# XL_N76E003K3__POWER_V17.net
KiCad netlist of a schematic drawn in Altium Designer
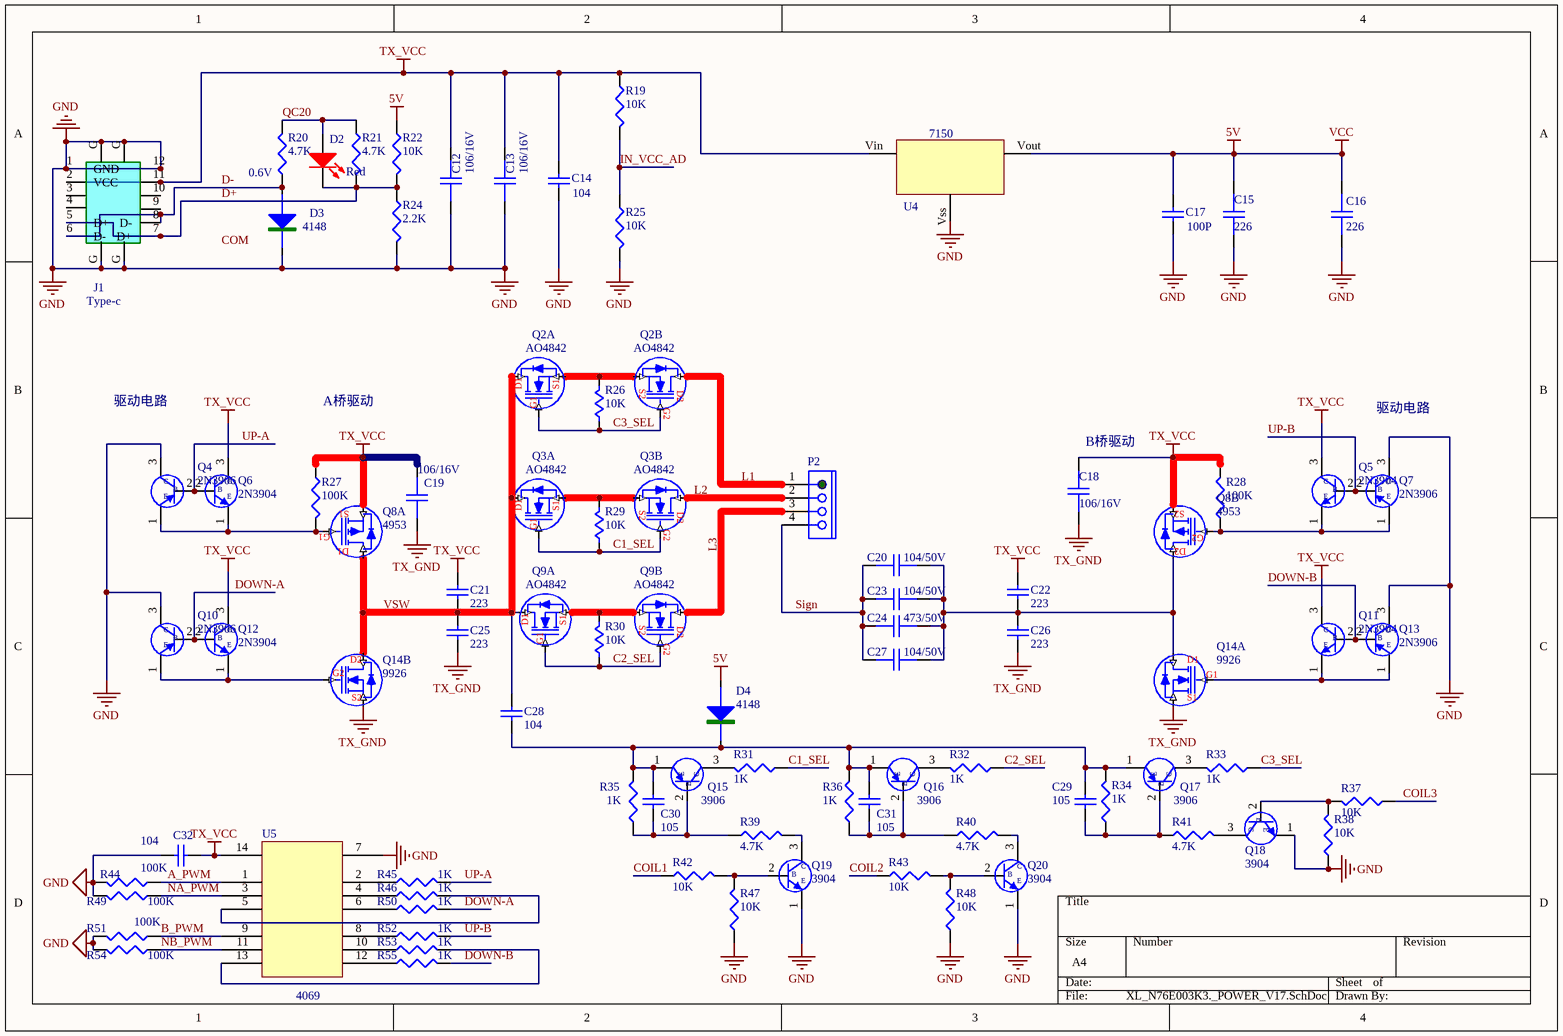
[diagram p0: XL_N76E003K3._POWER_V17.SchDoc]

(export (version "E")
  (design (tool "Eeschema 10.0.6"))
  (components
    (comp (ref "C12") (value "106/16V") (footprint "C0805") (libsource (lib "*") (part "CH")))
    (comp (ref "C13") (value "106/16V") (footprint "C0805") (libsource (lib "*") (part "CH")))
    (comp (ref "C14")
      (value "104")
      (footprint "C0402")
      (description "Capacitor")
      (fields (field (name "PUBLISHER") "Altium Limited"))
      (libsource (lib "*") (part "Cap"))
    )
    (comp (ref "C15") (value "226") (footprint "C0805") (libsource (lib "*") (part "CH")))
    (comp (ref "C16") (value "226") (footprint "C0805") (libsource (lib "*") (part "CH")))
    (comp (ref "C17")
      (value "100P")
      (footprint "C0402")
      (description "Capacitor")
      (fields (field (name "PUBLISHER") "Altium Limited"))
      (libsource (lib "*") (part "Cap"))
    )
    (comp (ref "C18") (value "106/16V") (footprint "C0805") (libsource (lib "*") (part "CH")))
    (comp (ref "C19") (value "106/16V") (footprint "C0805") (libsource (lib "*") (part "CH")))
    (comp (ref "C20") (value "104/50V") (footprint "C1206") (libsource (lib "*") (part "CH")))
    (comp (ref "C21")
      (value "223")
      (footprint "C1206")
      (description "Capacitor")
      (fields (field (name "PUBLISHER") "Altium Limited"))
      (libsource (lib "*") (part "Cap"))
    )
    (comp (ref "C22")
      (value "223")
      (footprint "C1206")
      (description "Capacitor")
      (fields (field (name "PUBLISHER") "Altium Limited"))
      (libsource (lib "*") (part "Cap"))
    )
    (comp (ref "C23") (value "104/50V") (footprint "C1206") (libsource (lib "*") (part "CH")))
    (comp (ref "C24") (value "473/50V") (footprint "C1206") (libsource (lib "*") (part "CH")))
    (comp (ref "C25")
      (value "223")
      (footprint "C0402")
      (description "Capacitor")
      (fields (field (name "PUBLISHER") "Altium Limited"))
      (libsource (lib "*") (part "Cap"))
    )
    (comp (ref "C26")
      (value "223")
      (footprint "C1206")
      (description "Capacitor")
      (fields (field (name "PUBLISHER") "Altium Limited"))
      (libsource (lib "*") (part "Cap"))
    )
    (comp (ref "C27") (value "104/50V") (footprint "C1206") (libsource (lib "*") (part "CH")))
    (comp (ref "C28")
      (value "104")
      (footprint "C0402")
      (description "Capacitor")
      (fields (field (name "PUBLISHER") "Altium Limited"))
      (libsource (lib "*") (part "Cap"))
    )
    (comp (ref "C29")
      (value "105")
      (footprint "C0402")
      (description "Capacitor")
      (fields (field (name "PUBLISHER") "Altium Limited"))
      (libsource (lib "*") (part "Cap"))
    )
    (comp (ref "C30")
      (value "105")
      (footprint "C0402")
      (description "Capacitor")
      (fields (field (name "PUBLISHER") "Altium Limited"))
      (libsource (lib "*") (part "Cap"))
    )
    (comp (ref "C31")
      (value "105")
      (footprint "C0402")
      (description "Capacitor")
      (fields (field (name "PUBLISHER") "Altium Limited"))
      (libsource (lib "*") (part "Cap"))
    )
    (comp (ref "C32")
      (value "104")
      (footprint "C0402")
      (description "Capacitor")
      (fields (field (name "PUBLISHER") "Altium Limited"))
      (libsource (lib "*") (part "Cap"))
    )
    (comp (ref "D2") (value "Red") (footprint "LED0603") (libsource (lib "XiaoQiang") (part "LED02")))
    (comp (ref "D3")
      (value "4148")
      (footprint "SOD323")
      (description "1N4001")
      (libsource (lib "*") (part "D0"))
    )
    (comp (ref "D4")
      (value "4148")
      (footprint "SOD323")
      (description "1N4001")
      (libsource (lib "*") (part "D0"))
    )
    (comp (ref "J1") (value "Type-c") (footprint "USB -MRO17") (libsource (lib "Xin Lang") (part "USP12P")))
    (comp (ref "P2") (value "~") (footprint "USB -MRO18-2") (libsource (lib "Xin Lang") (part "CON4")))
    (comp (ref "Q2") (value "AO4842") (footprint "SOP8D") (libsource (lib "lxzschlib") (part "MOSFETN2")))
    (comp (ref "Q3") (value "AO4842") (footprint "SOP8D") (libsource (lib "lxzschlib") (part "MOSFETN2")))
    (comp (ref "Q4") (value "2N3906") (footprint "SOT-23") (libsource (lib "Xin Lang") (part "PNP01")))
    (comp (ref "Q5") (value "2N3904") (footprint "SOT-23") (libsource (lib "Xin Lang") (part "NPN01")))
    (comp (ref "Q6") (value "2N3904") (footprint "SOT-23") (libsource (lib "") (part "NPN01_1")))
    (comp (ref "Q7") (value "2N3906") (footprint "SOT-23") (libsource (lib "") (part "PNP01_1")))
    (comp (ref "Q8") (value "4953") (footprint "SOP8D") (libsource (lib "lxzschlib") (part "MOSFETP2")))
    (comp (ref "Q9") (value "AO4842") (footprint "SOP8D") (libsource (lib "") (part "MOSFETN2_1")))
    (comp (ref "Q10") (value "2N3906") (footprint "SOT-23") (libsource (lib "Xin Lang") (part "PNP01")))
    (comp (ref "Q11") (value "2N3904") (footprint "SOT-23") (libsource (lib "Xin Lang") (part "NPN01")))
    (comp (ref "Q12") (value "2N3904") (footprint "SOT-23") (libsource (lib "") (part "NPN01_1")))
    (comp (ref "Q13") (value "2N3906") (footprint "SOT-23") (libsource (lib "") (part "PNP01_1")))
    (comp (ref "Q14") (value "9926") (footprint "SOP8D") (libsource (lib "") (part "MOSFETN2_1")))
    (comp (ref "Q15") (value "3906") (footprint "SOT-23") (libsource (lib "XiaoQiang") (part "PNP01")))
    (comp (ref "Q16") (value "3906") (footprint "SOT-23") (libsource (lib "XiaoQiang") (part "PNP01")))
    (comp (ref "Q17") (value "3906") (footprint "SOT-23") (libsource (lib "XiaoQiang") (part "PNP01")))
    (comp (ref "Q18") (value "3904") (footprint "SOT-23") (libsource (lib "") (part "NPN01_1")))
    (comp (ref "Q19") (value "3904") (footprint "SOT-23") (libsource (lib "XiaoQiang") (part "NPN01")))
    (comp (ref "Q20") (value "3904") (footprint "SOT-23") (libsource (lib "XiaoQiang") (part "NPN01")))
    (comp (ref "R19") (value "10K") (footprint "R0402") (description "1K") (libsource (lib "*") (part "R")))
    (comp (ref "R20") (value "4.7K") (footprint "R0402") (description "1K") (libsource (lib "*") (part "R")))
    (comp (ref "R21") (value "4.7K") (footprint "R0402") (description "1K") (libsource (lib "*") (part "R")))
    (comp (ref "R22") (value "10K") (footprint "R0402") (description "1K") (libsource (lib "*") (part "R")))
    (comp (ref "R24") (value "2.2K") (footprint "R0402") (description "1K") (libsource (lib "*") (part "R")))
    (comp (ref "R25") (value "10K") (footprint "R0402") (description "1K") (libsource (lib "*") (part "R")))
    (comp (ref "R26") (value "10K") (footprint "R0402") (libsource (lib "XiaoQiang") (part "Res01")))
    (comp (ref "R27") (value "100K") (footprint "R0402") (description "1K") (libsource (lib "*") (part "R")))
    (comp (ref "R28") (value "100K") (footprint "R0402") (description "1K") (libsource (lib "*") (part "R")))
    (comp (ref "R29") (value "10K") (footprint "R0402") (libsource (lib "XiaoQiang") (part "Res01")))
    (comp (ref "R30") (value "10K") (footprint "R0402") (libsource (lib "XiaoQiang") (part "Res01")))
    (comp (ref "R31") (value "1K") (footprint "R0402") (libsource (lib "*") (part "R")))
    (comp (ref "R32") (value "1K") (footprint "R0402") (libsource (lib "*") (part "R")))
    (comp (ref "R33") (value "1K") (footprint "R0402") (libsource (lib "*") (part "R")))
    (comp (ref "R34") (value "1K") (footprint "R0402") (libsource (lib "*") (part "R")))
    (comp (ref "R35") (value "1K") (footprint "R0402") (libsource (lib "*") (part "R")))
    (comp (ref "R36") (value "1K") (footprint "R0402") (libsource (lib "*") (part "R")))
    (comp (ref "R37") (value "10K") (footprint "R0402") (description "1K") (libsource (lib "*") (part "R")))
    (comp (ref "R38") (value "10K") (footprint "R0402") (description "1K") (libsource (lib "*") (part "R")))
    (comp (ref "R39") (value "4.7K") (footprint "R0402") (description "1K") (libsource (lib "*") (part "R")))
    (comp (ref "R40") (value "4.7K") (footprint "R0402") (description "1K") (libsource (lib "*") (part "R")))
    (comp (ref "R41") (value "4.7K") (footprint "R0402") (description "1K") (libsource (lib "*") (part "R")))
    (comp (ref "R42") (value "10K") (footprint "R0402") (description "1K") (libsource (lib "*") (part "R")))
    (comp (ref "R43") (value "10K") (footprint "R0402") (description "1K") (libsource (lib "*") (part "R")))
    (comp (ref "R44") (value "100K") (footprint "R0402") (description "1K") (libsource (lib "*") (part "R")))
    (comp (ref "R45") (value "1K") (footprint "R0402") (libsource (lib "*") (part "R")))
    (comp (ref "R46") (value "1K") (footprint "R0402") (libsource (lib "*") (part "R")))
    (comp (ref "R47") (value "10K") (footprint "R0402") (description "1K") (libsource (lib "*") (part "R")))
    (comp (ref "R48") (value "10K") (footprint "R0402") (description "1K") (libsource (lib "*") (part "R")))
    (comp (ref "R49") (value "100K") (footprint "R0402") (description "1K") (libsource (lib "*") (part "R")))
    (comp (ref "R50") (value "1K") (footprint "R0402") (libsource (lib "*") (part "R")))
    (comp (ref "R51") (value "100K") (footprint "R0402") (description "1K") (libsource (lib "*") (part "R")))
    (comp (ref "R52") (value "1K") (footprint "R0402") (libsource (lib "*") (part "R")))
    (comp (ref "R53") (value "1K") (footprint "R0402") (libsource (lib "*") (part "R")))
    (comp (ref "R54") (value "100K") (footprint "R0402") (description "1K") (libsource (lib "*") (part "R")))
    (comp (ref "R55") (value "1K") (footprint "R0402") (libsource (lib "*") (part "R")))
    (comp (ref "U4") (value "7150") (footprint "SOT-23-7150") (libsource (lib "*") (part "VOLTREG")))
    (comp (ref "U5") (value "4069") (footprint "SOP14") (libsource (lib "Schlib1") (part "CD4069")))
  )
  (nets
    (net (code "1") (name "/A_PWM") (class "Default")
      (node (ref "R44") (pin "1") (pintype "passive"))
      (node (ref "U5") (pin "1") (pintype "passive"))
    )
    (net (code "2") (name "/B_PWM") (class "Default")
      (node (ref "R51") (pin "1") (pintype "passive"))
      (node (ref "U5") (pin "9") (pintype "passive"))
    )
    (net (code "3") (name "/C1_SEL") (class "Default")
      (node (ref "Q3") (pin "B1") (pinfunction "G1_B1") (pintype "input"))
      (node (ref "Q3") (pin "B2") (pinfunction "G2_B2") (pintype "input"))
      (node (ref "R29") (pin "1") (pinfunction "1_1") (pintype "passive"))
      (node (ref "R31") (pin "1") (pintype "passive"))
    )
    (net (code "4") (name "/C2_SEL") (class "Default")
      (node (ref "Q9") (pin "B1") (pinfunction "G1_B1") (pintype "input"))
      (node (ref "Q9") (pin "B2") (pinfunction "G2_B2") (pintype "input"))
      (node (ref "R30") (pin "1") (pinfunction "1_1") (pintype "passive"))
      (node (ref "R32") (pin "1") (pintype "passive"))
    )
    (net (code "5") (name "/C3_SEL") (class "Default")
      (node (ref "Q2") (pin "B1") (pinfunction "G1_B1") (pintype "input"))
      (node (ref "Q2") (pin "B2") (pinfunction "G2_B2") (pintype "input"))
      (node (ref "R26") (pin "1") (pinfunction "1_1") (pintype "passive"))
      (node (ref "R33") (pin "1") (pintype "passive"))
    )
    (net (code "6") (name "/COIL1") (class "Default") (node (ref "R42") (pin "1") (pintype "passive")))
    (net (code "7") (name "/COIL2") (class "Default") (node (ref "R43") (pin "1") (pintype "passive")))
    (net (code "8") (name "/COIL3") (class "Default") (node (ref "R37") (pin "1") (pintype "passive")))
    (net (code "10") (name "/D+") (class "Default")
      (node (ref "D2") (pin "2") (pinfunction "K_2") (pintype "passive"))
      (node (ref "J1") (pin "5") (pinfunction "D+_5") (pintype "passive"))
      (node (ref "J1") (pin "7") (pinfunction "D+_7") (pintype "passive"))
      (node (ref "R21") (pin "1") (pintype "passive"))
      (node (ref "R22") (pin "1") (pintype "passive"))
      (node (ref "R24") (pin "2") (pintype "passive"))
    )
    (net (code "11") (name "/D-") (class "Default")
      (node (ref "D3") (pin "1") (pintype "passive"))
      (node (ref "J1") (pin "6") (pinfunction "D-_6") (pintype "passive"))
      (node (ref "J1") (pin "8") (pinfunction "D-_8") (pintype "passive"))
      (node (ref "R20") (pin "2") (pintype "passive"))
    )
    (net (code "12") (name "/DOWN-A") (class "Default")
      (node (ref "Q10") (pin "2") (pinfunction "B_2") (pintype "passive"))
      (node (ref "Q12") (pin "2") (pinfunction "B_2") (pintype "passive"))
      (node (ref "R50") (pin "2") (pintype "passive"))
    )
    (net (code "13") (name "/DOWN-B") (class "Default")
      (node (ref "Q11") (pin "2") (pinfunction "B_2") (pintype "passive"))
      (node (ref "Q13") (pin "2") (pinfunction "B_2") (pintype "passive"))
      (node (ref "R55") (pin "2") (pintype "passive"))
    )
    (net (code "14") (name "/IN_VCC_AD") (class "Default")
      (node (ref "R19") (pin "1") (pintype "passive"))
      (node (ref "R25") (pin "2") (pintype "passive"))
    )
    (net (code "15") (name "/L1") (class "Default")
      (node (ref "P2") (pin "1") (pintype "passive"))
      (node (ref "Q2") (pin "C2") (pinfunction "D2_C2") (pintype "input"))
    )
    (net (code "16") (name "/L2") (class "Default")
      (node (ref "P2") (pin "2") (pintype "passive"))
      (node (ref "Q3") (pin "C2") (pinfunction "D2_C2") (pintype "input"))
    )
    (net (code "17") (name "/L3") (class "Default")
      (node (ref "P2") (pin "3") (pintype "passive"))
      (node (ref "Q9") (pin "C2") (pinfunction "D2_C2") (pintype "input"))
    )
    (net (code "18") (name "/NA_PWM") (class "Default")
      (node (ref "R49") (pin "1") (pintype "passive"))
      (node (ref "U5") (pin "3") (pintype "passive"))
    )
    (net (code "19") (name "/NB_PWM") (class "Default")
      (node (ref "R54") (pin "1") (pintype "passive"))
      (node (ref "U5") (pin "11") (pintype "passive"))
    )
    (net (code "20") (name "/QC20") (class "Default")
      (node (ref "D2") (pin "1") (pinfunction "A_1") (pintype "passive"))
      (node (ref "R20") (pin "1") (pintype "passive"))
      (node (ref "R21") (pin "2") (pintype "passive"))
    )
    (net (code "21") (name "/Sign") (class "Default")
      (node (ref "C20") (pin "1") (pintype "passive"))
      (node (ref "C23") (pin "1") (pintype "passive"))
      (node (ref "C24") (pin "1") (pintype "passive"))
      (node (ref "C27") (pin "1") (pintype "passive"))
      (node (ref "P2") (pin "4") (pintype "passive"))
    )
    (net (code "22") (name "/UP-A") (class "Default")
      (node (ref "Q4") (pin "2") (pinfunction "B_2") (pintype "passive"))
      (node (ref "Q6") (pin "2") (pinfunction "B_2") (pintype "passive"))
      (node (ref "R45") (pin "2") (pintype "passive"))
    )
    (net (code "23") (name "/UP-B") (class "Default")
      (node (ref "Q5") (pin "2") (pinfunction "B_2") (pintype "passive"))
      (node (ref "Q7") (pin "2") (pinfunction "B_2") (pintype "passive"))
      (node (ref "R52") (pin "2") (pintype "passive"))
    )
    (net (code "24") (name "/VSW") (class "Default")
      (node (ref "C21") (pin "1") (pinfunction "1_1") (pintype "passive"))
      (node (ref "C25") (pin "2") (pinfunction "2_2") (pintype "passive"))
      (node (ref "C28") (pin "1") (pinfunction "1_1") (pintype "passive"))
      (node (ref "Q14") (pin "C2") (pinfunction "D2_C2") (pintype "input"))
      (node (ref "Q2") (pin "C1") (pinfunction "D1_C1") (pintype "input"))
      (node (ref "Q3") (pin "C1") (pinfunction "D1_C1") (pintype "input"))
      (node (ref "Q8") (pin "C1") (pinfunction "D1_C1") (pintype "input"))
      (node (ref "Q9") (pin "C1") (pinfunction "D1_C1") (pintype "input"))
    )
    (net (code "25") (name "5V") (class "Default")
      (node (ref "C15") (pin "1") (pintype "passive"))
      (node (ref "C16") (pin "2") (pintype "passive"))
      (node (ref "C17") (pin "1") (pinfunction "1_1") (pintype "passive"))
      (node (ref "D4") (pin "1") (pintype "passive"))
      (node (ref "R22") (pin "2") (pintype "passive"))
      (node (ref "U4") (pin "Vout") (pintype "passive"))
    )
    (net (code "26") (name "GND") (class "Default")
      (node (ref "C12") (pin "2") (pintype "passive"))
      (node (ref "C13") (pin "2") (pintype "passive"))
      (node (ref "C14") (pin "2") (pinfunction "2_2") (pintype "passive"))
      (node (ref "C15") (pin "2") (pintype "passive"))
      (node (ref "C16") (pin "1") (pintype "passive"))
      (node (ref "C17") (pin "2") (pinfunction "2_2") (pintype "passive"))
      (node (ref "C32") (pin "1") (pinfunction "1_1") (pintype "passive"))
      (node (ref "D3") (pin "2") (pintype "passive"))
      (node (ref "J1") (pin "1") (pinfunction "GND_1") (pintype "passive"))
      (node (ref "J1") (pin "12") (pintype "passive"))
      (node (ref "J1") (pin "G") (pintype "passive"))
      (node (ref "Q10") (pin "3") (pinfunction "C_3") (pintype "passive"))
      (node (ref "Q13") (pin "3") (pinfunction "C_3") (pintype "passive"))
      (node (ref "Q18") (pin "1") (pinfunction "E_1") (pintype "passive"))
      (node (ref "Q19") (pin "1") (pinfunction "E_1") (pintype "passive"))
      (node (ref "Q20") (pin "1") (pinfunction "E_1") (pintype "passive"))
      (node (ref "Q4") (pin "3") (pinfunction "C_3") (pintype "passive"))
      (node (ref "Q7") (pin "3") (pinfunction "C_3") (pintype "passive"))
      (node (ref "R24") (pin "1") (pintype "passive"))
      (node (ref "R25") (pin "1") (pintype "passive"))
      (node (ref "R38") (pin "1") (pintype "passive"))
      (node (ref "R44") (pin "2") (pintype "passive"))
      (node (ref "R47") (pin "1") (pintype "passive"))
      (node (ref "R48") (pin "1") (pintype "passive"))
      (node (ref "R49") (pin "2") (pintype "passive"))
      (node (ref "R51") (pin "2") (pintype "passive"))
      (node (ref "R54") (pin "2") (pintype "passive"))
      (node (ref "U4") (pin "Vss") (pintype "passive"))
      (node (ref "U5") (pin "7") (pintype "passive"))
    )
    (net (code "27") (name "Net-(Q2A-S1)") (class "Default")
      (node (ref "Q2") (pin "E1") (pinfunction "S1_E1") (pintype "input"))
      (node (ref "Q2") (pin "E2") (pinfunction "S2_E2") (pintype "input"))
      (node (ref "R26") (pin "2") (pinfunction "2_2") (pintype "passive"))
    )
    (net (code "28") (name "Net-(Q3A-S1)") (class "Default")
      (node (ref "Q3") (pin "E1") (pinfunction "S1_E1") (pintype "input"))
      (node (ref "Q3") (pin "E2") (pinfunction "S2_E2") (pintype "input"))
      (node (ref "R29") (pin "2") (pinfunction "2_2") (pintype "passive"))
    )
    (net (code "29") (name "Net-(Q4-E)") (class "Default")
      (node (ref "Q4") (pin "1") (pinfunction "E_1") (pintype "passive"))
      (node (ref "Q6") (pin "1") (pinfunction "E_1") (pintype "passive"))
      (node (ref "Q8") (pin "B1") (pinfunction "G1_B1") (pintype "input"))
      (node (ref "R27") (pin "2") (pintype "passive"))
    )
    (net (code "30") (name "Net-(Q5-E)") (class "Default")
      (node (ref "Q5") (pin "1") (pinfunction "E_1") (pintype "passive"))
      (node (ref "Q7") (pin "1") (pinfunction "E_1") (pintype "passive"))
      (node (ref "Q8") (pin "B2") (pinfunction "G2_B2") (pintype "input"))
      (node (ref "R28") (pin "1") (pintype "passive"))
    )
    (net (code "31") (name "Net-(Q9A-S1)") (class "Default")
      (node (ref "Q9") (pin "E1") (pinfunction "S1_E1") (pintype "input"))
      (node (ref "Q9") (pin "E2") (pinfunction "S2_E2") (pintype "input"))
      (node (ref "R30") (pin "2") (pinfunction "2_2") (pintype "passive"))
    )
    (net (code "32") (name "Net-(Q10-E)") (class "Default")
      (node (ref "Q10") (pin "1") (pinfunction "E_1") (pintype "passive"))
      (node (ref "Q12") (pin "1") (pinfunction "E_1") (pintype "passive"))
      (node (ref "Q14") (pin "B2") (pinfunction "G2_B2") (pintype "input"))
    )
    (net (code "33") (name "Net-(Q11-E)") (class "Default")
      (node (ref "Q11") (pin "1") (pinfunction "E_1") (pintype "passive"))
      (node (ref "Q13") (pin "1") (pinfunction "E_1") (pintype "passive"))
      (node (ref "Q14") (pin "B1") (pinfunction "G1_B1") (pintype "input"))
    )
    (net (code "34") (name "Net-(Q14A-D1)") (class "Default")
      (node (ref "C20") (pin "2") (pintype "passive"))
      (node (ref "C22") (pin "1") (pinfunction "1_1") (pintype "passive"))
      (node (ref "C23") (pin "2") (pintype "passive"))
      (node (ref "C24") (pin "2") (pintype "passive"))
      (node (ref "C26") (pin "2") (pinfunction "2_2") (pintype "passive"))
      (node (ref "C27") (pin "2") (pintype "passive"))
      (node (ref "Q14") (pin "C1") (pinfunction "D1_C1") (pintype "input"))
      (node (ref "Q8") (pin "C2") (pinfunction "D2_C2") (pintype "input"))
    )
    (net (code "35") (name "Net-(Q15-B)") (class "Default")
      (node (ref "C30") (pin "2") (pinfunction "2_2") (pintype "passive"))
      (node (ref "Q15") (pin "2") (pinfunction "B_2") (pintype "passive"))
      (node (ref "R35") (pin "1") (pintype "passive"))
      (node (ref "R39") (pin "1") (pintype "passive"))
    )
    (net (code "36") (name "Net-(Q15-C)") (class "Default")
      (node (ref "Q15") (pin "3") (pinfunction "C_3") (pintype "passive"))
      (node (ref "R31") (pin "2") (pintype "passive"))
    )
    (net (code "37") (name "Net-(Q15-E)") (class "Default")
      (node (ref "C28") (pin "2") (pinfunction "2_2") (pintype "passive"))
      (node (ref "C29") (pin "1") (pinfunction "1_1") (pintype "passive"))
      (node (ref "C30") (pin "1") (pinfunction "1_1") (pintype "passive"))
      (node (ref "C31") (pin "1") (pinfunction "1_1") (pintype "passive"))
      (node (ref "D4") (pin "2") (pintype "passive"))
      (node (ref "Q15") (pin "1") (pinfunction "E_1") (pintype "passive"))
      (node (ref "Q16") (pin "1") (pinfunction "E_1") (pintype "passive"))
      (node (ref "Q17") (pin "1") (pinfunction "E_1") (pintype "passive"))
      (node (ref "R34") (pin "2") (pintype "passive"))
      (node (ref "R35") (pin "2") (pintype "passive"))
      (node (ref "R36") (pin "2") (pintype "passive"))
    )
    (net (code "38") (name "Net-(Q16-B)") (class "Default")
      (node (ref "C31") (pin "2") (pinfunction "2_2") (pintype "passive"))
      (node (ref "Q16") (pin "2") (pinfunction "B_2") (pintype "passive"))
      (node (ref "R36") (pin "1") (pintype "passive"))
      (node (ref "R40") (pin "1") (pintype "passive"))
    )
    (net (code "39") (name "Net-(Q16-C)") (class "Default")
      (node (ref "Q16") (pin "3") (pinfunction "C_3") (pintype "passive"))
      (node (ref "R32") (pin "2") (pintype "passive"))
    )
    (net (code "40") (name "Net-(Q17-B)") (class "Default")
      (node (ref "C29") (pin "2") (pinfunction "2_2") (pintype "passive"))
      (node (ref "Q17") (pin "2") (pinfunction "B_2") (pintype "passive"))
      (node (ref "R34") (pin "1") (pintype "passive"))
      (node (ref "R41") (pin "1") (pintype "passive"))
    )
    (net (code "41") (name "Net-(Q17-C)") (class "Default")
      (node (ref "Q17") (pin "3") (pinfunction "C_3") (pintype "passive"))
      (node (ref "R33") (pin "2") (pintype "passive"))
    )
    (net (code "42") (name "Net-(Q18-B)") (class "Default")
      (node (ref "Q18") (pin "2") (pinfunction "B_2") (pintype "passive"))
      (node (ref "R37") (pin "2") (pintype "passive"))
      (node (ref "R38") (pin "2") (pintype "passive"))
    )
    (net (code "43") (name "Net-(Q18-C)") (class "Default")
      (node (ref "Q18") (pin "3") (pinfunction "C_3") (pintype "passive"))
      (node (ref "R41") (pin "2") (pintype "passive"))
    )
    (net (code "44") (name "Net-(Q19-B)") (class "Default")
      (node (ref "Q19") (pin "2") (pinfunction "B_2") (pintype "passive"))
      (node (ref "R42") (pin "2") (pintype "passive"))
      (node (ref "R47") (pin "2") (pintype "passive"))
    )
    (net (code "45") (name "Net-(Q19-C)") (class "Default")
      (node (ref "Q19") (pin "3") (pinfunction "C_3") (pintype "passive"))
      (node (ref "R39") (pin "2") (pintype "passive"))
    )
    (net (code "46") (name "Net-(Q20-B)") (class "Default")
      (node (ref "Q20") (pin "2") (pinfunction "B_2") (pintype "passive"))
      (node (ref "R43") (pin "2") (pintype "passive"))
      (node (ref "R48") (pin "2") (pintype "passive"))
    )
    (net (code "47") (name "Net-(Q20-C)") (class "Default")
      (node (ref "Q20") (pin "3") (pinfunction "C_3") (pintype "passive"))
      (node (ref "R40") (pin "2") (pintype "passive"))
    )
    (net (code "48") (name "Net-(R45-Pad1)") (class "Default")
      (node (ref "R45") (pin "1") (pintype "passive"))
      (node (ref "U5") (pin "2") (pintype "passive"))
    )
    (net (code "49") (name "Net-(R46-Pad1)") (class "Default")
      (node (ref "R46") (pin "1") (pintype "passive"))
      (node (ref "U5") (pin "4") (pintype "passive"))
    )
    (net (code "50") (name "Net-(R46-Pad2)") (class "Default")
      (node (ref "R46") (pin "2") (pintype "passive"))
      (node (ref "U5") (pin "5") (pintype "passive"))
    )
    (net (code "51") (name "Net-(R50-Pad1)") (class "Default")
      (node (ref "R50") (pin "1") (pintype "passive"))
      (node (ref "U5") (pin "6") (pintype "passive"))
    )
    (net (code "52") (name "Net-(R52-Pad1)") (class "Default")
      (node (ref "R52") (pin "1") (pintype "passive"))
      (node (ref "U5") (pin "8") (pintype "passive"))
    )
    (net (code "53") (name "Net-(R53-Pad1)") (class "Default")
      (node (ref "R53") (pin "1") (pintype "passive"))
      (node (ref "U5") (pin "10") (pintype "passive"))
    )
    (net (code "54") (name "Net-(R53-Pad2)") (class "Default")
      (node (ref "R53") (pin "2") (pintype "passive"))
      (node (ref "U5") (pin "13") (pintype "passive"))
    )
    (net (code "55") (name "Net-(R55-Pad1)") (class "Default")
      (node (ref "R55") (pin "1") (pintype "passive"))
      (node (ref "U5") (pin "12") (pintype "passive"))
    )
    (net (code "56") (name "TX_GND") (class "Default")
      (node (ref "C18") (pin "2") (pintype "passive"))
      (node (ref "C19") (pin "2") (pintype "passive"))
      (node (ref "C25") (pin "1") (pinfunction "1_1") (pintype "passive"))
      (node (ref "C26") (pin "1") (pinfunction "1_1") (pintype "passive"))
      (node (ref "Q14") (pin "E1") (pinfunction "S1_E1") (pintype "input"))
      (node (ref "Q14") (pin "E2") (pinfunction "S2_E2") (pintype "input"))
    )
    (net (code "57") (name "TX_VCC") (class "Default")
      (node (ref "C12") (pin "1") (pintype "passive"))
      (node (ref "C13") (pin "1") (pintype "passive"))
      (node (ref "C14") (pin "1") (pinfunction "1_1") (pintype "passive"))
      (node (ref "C18") (pin "1") (pintype "passive"))
      (node (ref "C19") (pin "1") (pintype "passive"))
      (node (ref "C21") (pin "2") (pinfunction "2_2") (pintype "passive"))
      (node (ref "C22") (pin "2") (pinfunction "2_2") (pintype "passive"))
      (node (ref "C32") (pin "2") (pinfunction "2_2") (pintype "passive"))
      (node (ref "J1") (pin "11") (pintype "passive"))
      (node (ref "J1") (pin "2") (pinfunction "VCC_2") (pintype "passive"))
      (node (ref "Q11") (pin "3") (pinfunction "C_3") (pintype "passive"))
      (node (ref "Q12") (pin "3") (pinfunction "C_3") (pintype "passive"))
      (node (ref "Q5") (pin "3") (pinfunction "C_3") (pintype "passive"))
      (node (ref "Q6") (pin "3") (pinfunction "C_3") (pintype "passive"))
      (node (ref "Q8") (pin "E1") (pinfunction "S1_E1") (pintype "input"))
      (node (ref "Q8") (pin "E2") (pinfunction "S2_E2") (pintype "input"))
      (node (ref "R19") (pin "2") (pintype "passive"))
      (node (ref "R27") (pin "1") (pintype "passive"))
      (node (ref "R28") (pin "2") (pintype "passive"))
      (node (ref "U4") (pin "Vin") (pintype "passive"))
      (node (ref "U5") (pin "14") (pintype "passive"))
    )
    (net (code "58") (name "unconnected-(J1-Pad3)") (class "Default")
      (node (ref "J1") (pin "3") (pintype "passive"))
    )
    (net (code "59") (name "unconnected-(J1-Pad4)") (class "Default")
      (node (ref "J1") (pin "4") (pintype "passive"))
    )
    (net (code "60") (name "unconnected-(J1-Pad9)") (class "Default")
      (node (ref "J1") (pin "9") (pintype "passive"))
    )
    (net (code "61") (name "unconnected-(J1-Pad10)") (class "Default")
      (node (ref "J1") (pin "10") (pintype "passive"))
    )
  )
)
